# mini_screen.net
KiCad netlist of a schematic drawn in EasyEDA Pro
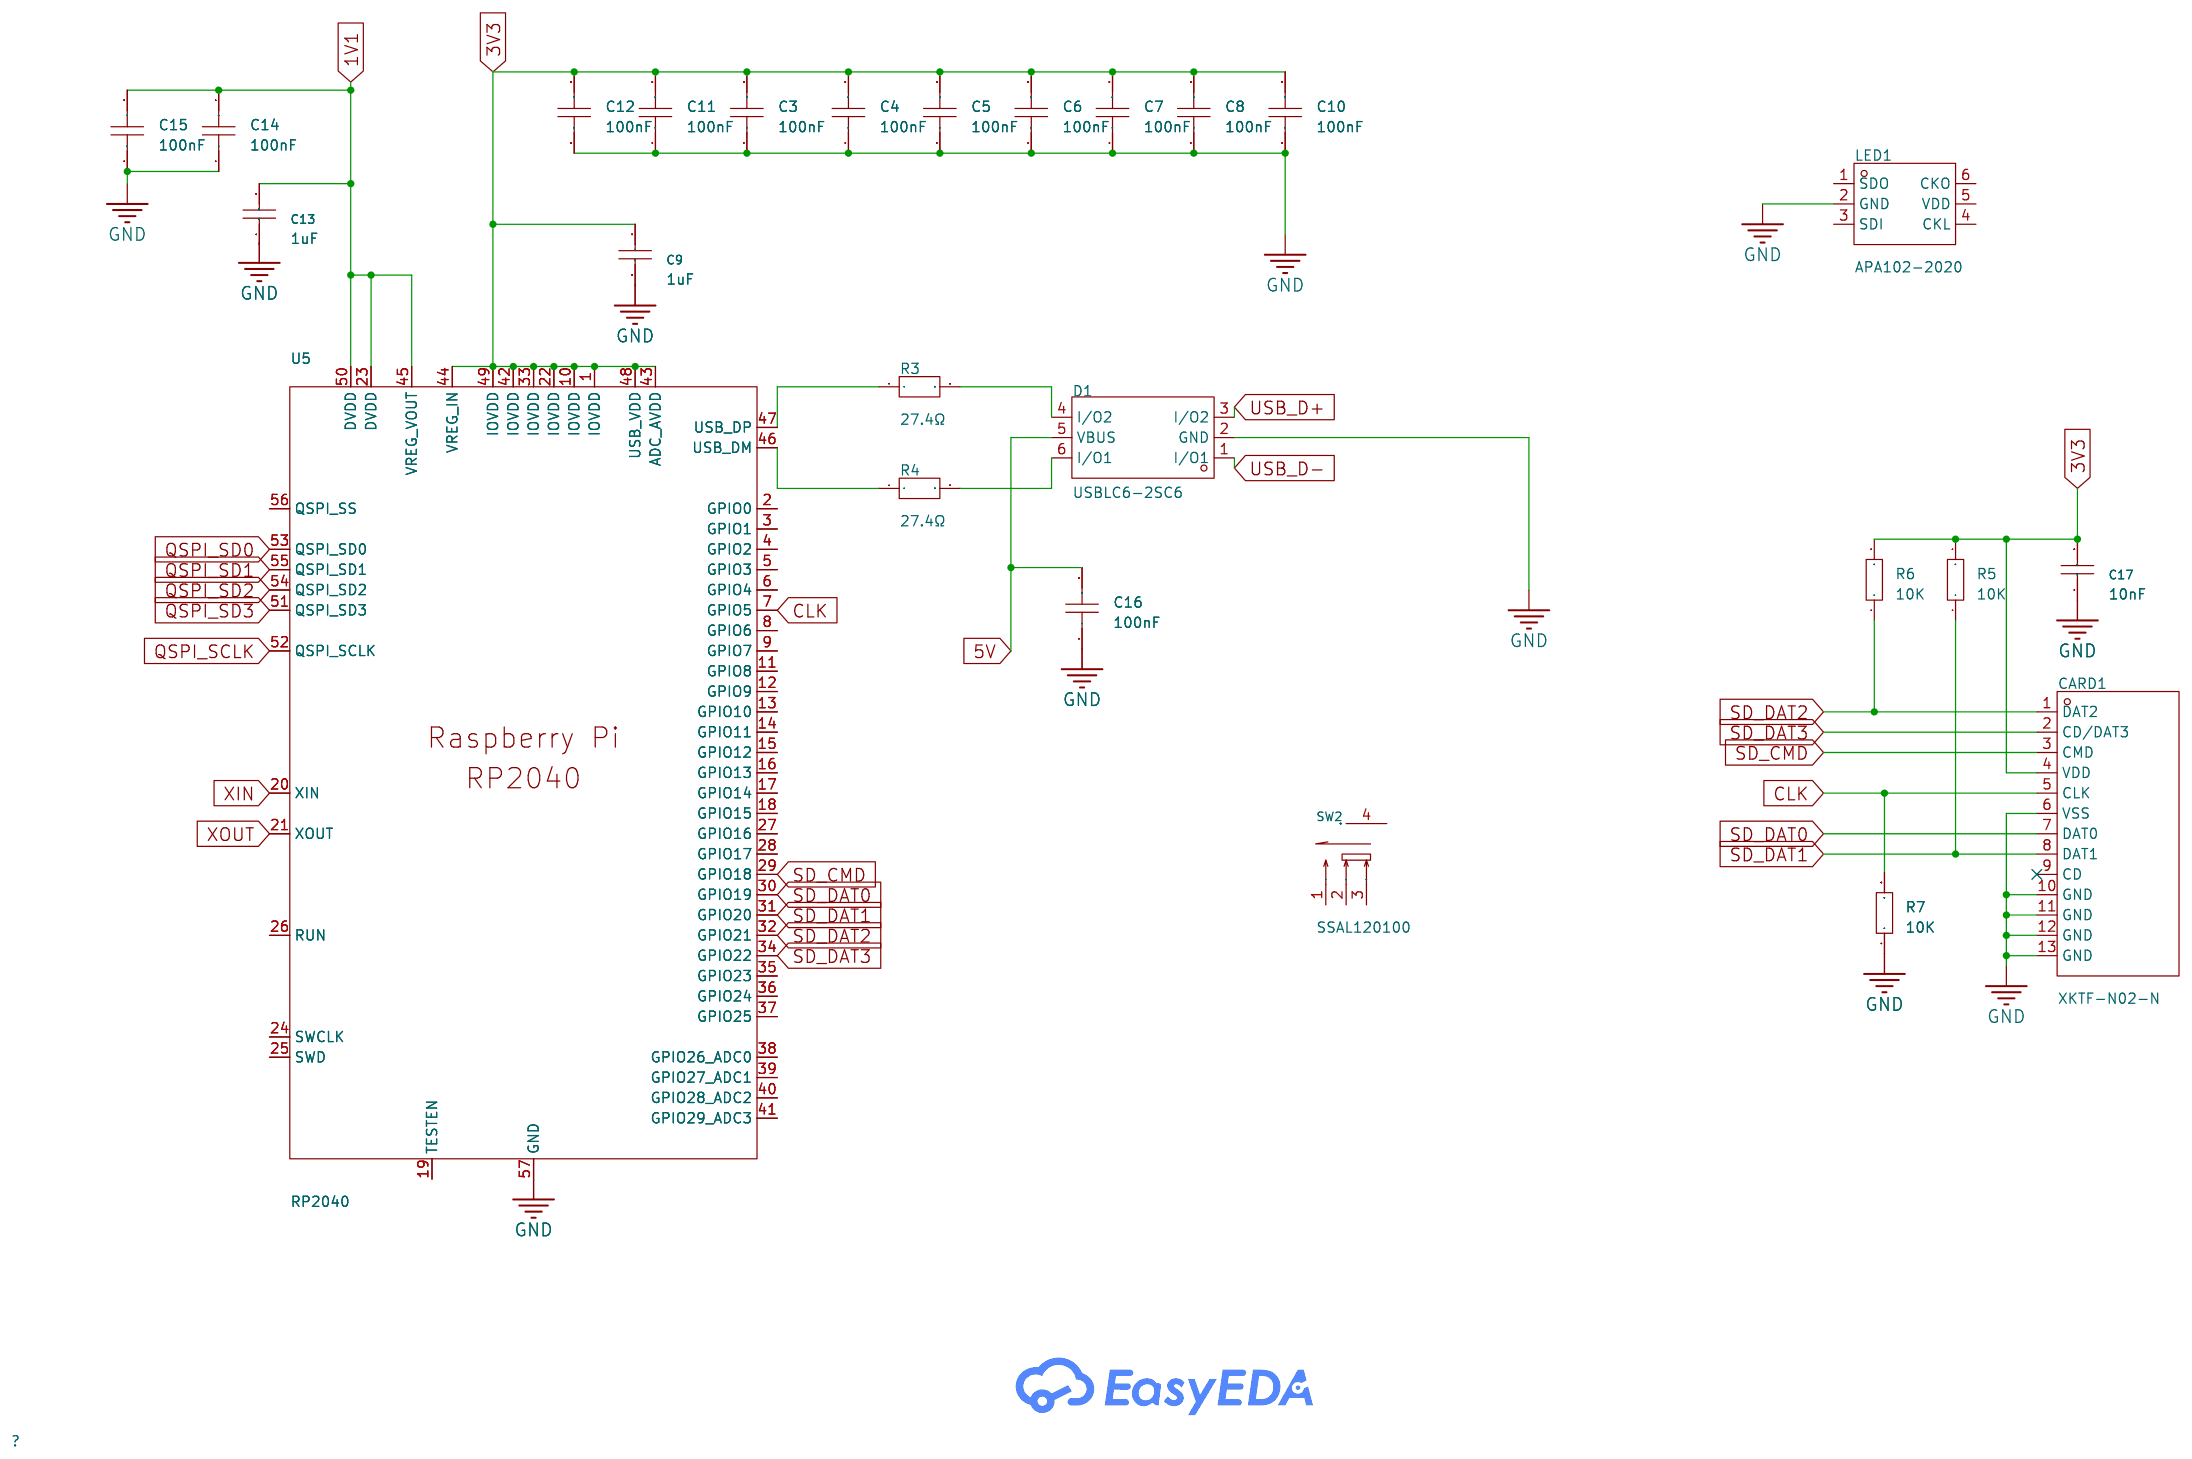
[diagram p0: rp2040]
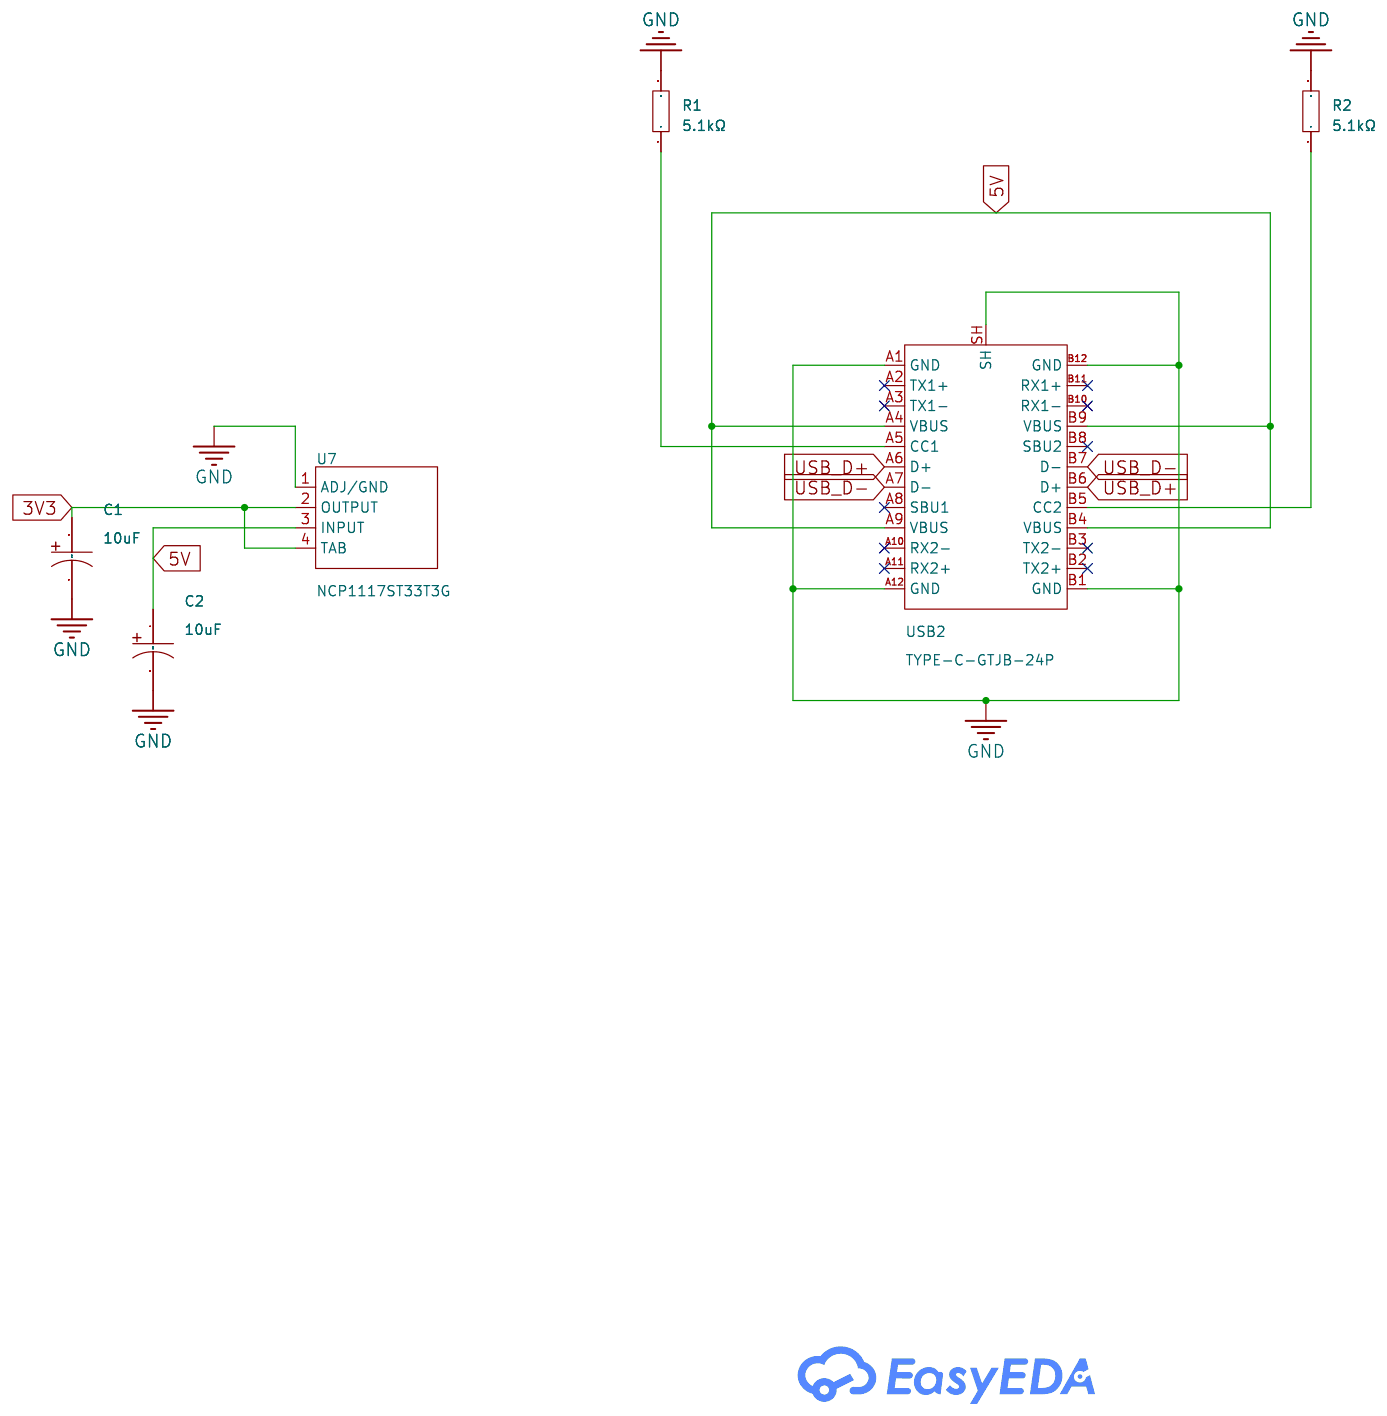
[diagram p1: usbc]
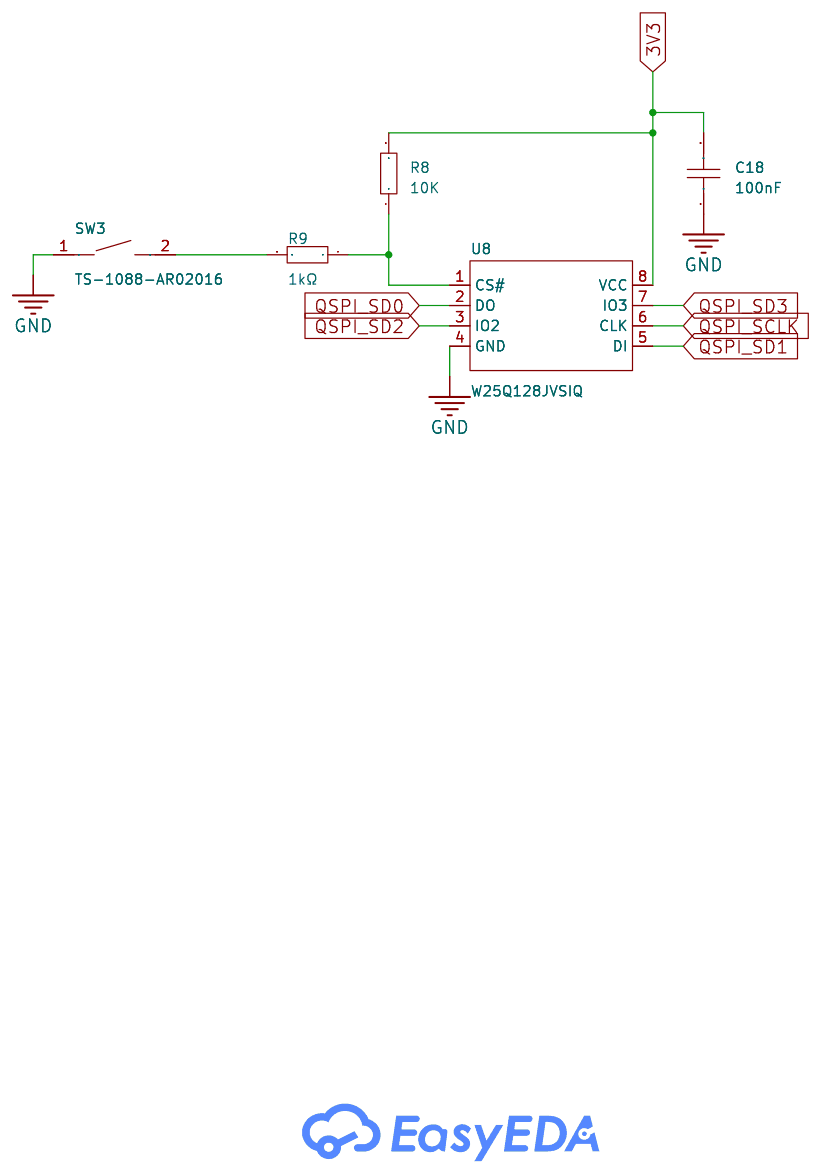
[diagram p2: nand flash]
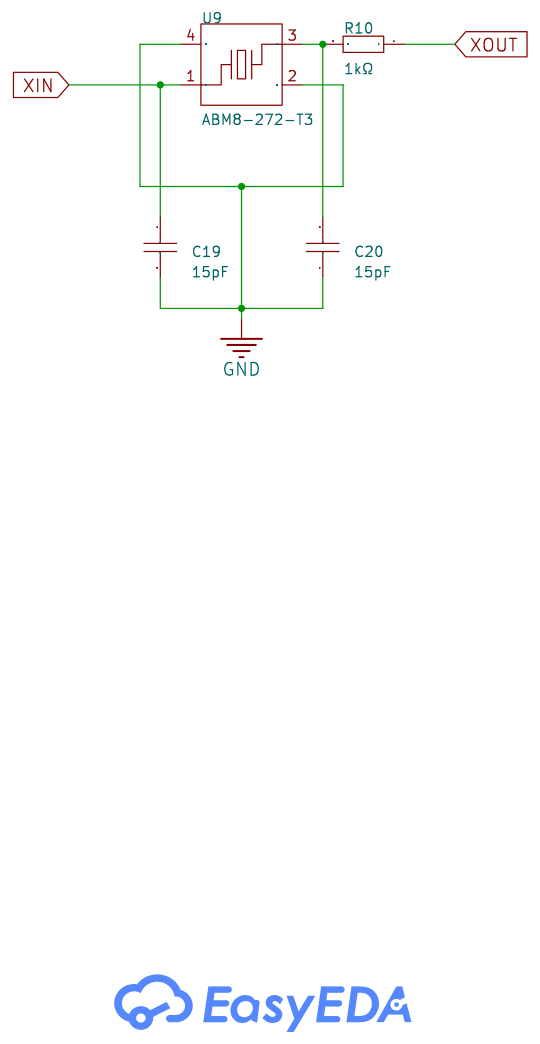
[diagram p3: clock]

(export (version "E")
  (design (tool "Eeschema 10.0.6"))
  (components
    (comp (ref "C3")
      (value "100nF")
      (footprint "easyedapro:C0805")
      (description "Capacitance:100nF Tolerance:±10% Tolerance:±10% Voltage Rating:50V Temperature Coefficient:X7R")
      (fields
        (field (name "Manufacturer Part") "CC0805KRX7R9BB104")
        (field (name "Manufacturer") "YAGEO(国巨)")
      )
      (libsource (lib "easyedapro") (part "CC0805KRX7R9BB104"))
    )
    (comp (ref "C4")
      (value "100nF")
      (footprint "easyedapro:C0805")
      (description "Capacitance:100nF Tolerance:±10% Tolerance:±10% Voltage Rating:50V Temperature Coefficient:X7R")
      (fields
        (field (name "Manufacturer Part") "CC0805KRX7R9BB104")
        (field (name "Manufacturer") "YAGEO(国巨)")
      )
      (libsource (lib "easyedapro") (part "CC0805KRX7R9BB104"))
    )
    (comp (ref "C5")
      (value "100nF")
      (footprint "easyedapro:C0805")
      (description "Capacitance:100nF Tolerance:±10% Tolerance:±10% Voltage Rating:50V Temperature Coefficient:X7R")
      (fields
        (field (name "Manufacturer Part") "CC0805KRX7R9BB104")
        (field (name "Manufacturer") "YAGEO(国巨)")
      )
      (libsource (lib "easyedapro") (part "CC0805KRX7R9BB104"))
    )
    (comp (ref "C6")
      (value "100nF")
      (footprint "easyedapro:C0805")
      (description "Capacitance:100nF Tolerance:±10% Tolerance:±10% Voltage Rating:50V Temperature Coefficient:X7R")
      (fields
        (field (name "Manufacturer Part") "CC0805KRX7R9BB104")
        (field (name "Manufacturer") "YAGEO(国巨)")
      )
      (libsource (lib "easyedapro") (part "CC0805KRX7R9BB104"))
    )
    (comp (ref "C7")
      (value "100nF")
      (footprint "easyedapro:C0805")
      (description "Capacitance:100nF Tolerance:±10% Tolerance:±10% Voltage Rating:50V Temperature Coefficient:X7R")
      (fields
        (field (name "Manufacturer Part") "CC0805KRX7R9BB104")
        (field (name "Manufacturer") "YAGEO(国巨)")
      )
      (libsource (lib "easyedapro") (part "CC0805KRX7R9BB104"))
    )
    (comp (ref "C8")
      (value "100nF")
      (footprint "easyedapro:C0805")
      (description "Capacitance:100nF Tolerance:±10% Tolerance:±10% Voltage Rating:50V Temperature Coefficient:X7R")
      (fields
        (field (name "Manufacturer Part") "CC0805KRX7R9BB104")
        (field (name "Manufacturer") "YAGEO(国巨)")
      )
      (libsource (lib "easyedapro") (part "CC0805KRX7R9BB104"))
    )
    (comp (ref "C9")
      (value "1uF")
      (footprint "easyedapro:C0805")
      (description "Capacitance:1uF Tolerance:±10% Tolerance:±10% Voltage Rating:50V Temperature Coefficient:X7R")
      (fields
        (field (name "Manufacturer Part") "CL21B105KBFNNNE")
        (field (name "Manufacturer") "SAMSUNG(三星)")
      )
      (libsource (lib "easyedapro") (part "CL21B105KBFNNNE"))
    )
    (comp (ref "C10")
      (value "100nF")
      (footprint "easyedapro:C0805")
      (description "Capacitance:100nF Tolerance:±10% Tolerance:±10% Voltage Rating:50V Temperature Coefficient:X7R")
      (fields
        (field (name "Manufacturer Part") "CC0805KRX7R9BB104")
        (field (name "Manufacturer") "YAGEO(国巨)")
      )
      (libsource (lib "easyedapro") (part "CC0805KRX7R9BB104"))
    )
    (comp (ref "C11")
      (value "100nF")
      (footprint "easyedapro:C0805")
      (description "Capacitance:100nF Tolerance:±10% Tolerance:±10% Voltage Rating:50V Temperature Coefficient:X7R")
      (fields
        (field (name "Manufacturer Part") "CC0805KRX7R9BB104")
        (field (name "Manufacturer") "YAGEO(国巨)")
      )
      (libsource (lib "easyedapro") (part "CC0805KRX7R9BB104"))
    )
    (comp (ref "C12")
      (value "100nF")
      (footprint "easyedapro:C0805")
      (description "Capacitance:100nF Tolerance:±10% Tolerance:±10% Voltage Rating:50V Temperature Coefficient:X7R")
      (fields
        (field (name "Manufacturer Part") "CC0805KRX7R9BB104")
        (field (name "Manufacturer") "YAGEO(国巨)")
      )
      (libsource (lib "easyedapro") (part "CC0805KRX7R9BB104"))
    )
    (comp (ref "C13")
      (value "1uF")
      (footprint "easyedapro:C0805")
      (description "Capacitance:1uF Tolerance:±10% Tolerance:±10% Voltage Rating:50V Temperature Coefficient:X7R")
      (fields
        (field (name "Manufacturer Part") "CL21B105KBFNNNE")
        (field (name "Manufacturer") "SAMSUNG(三星)")
      )
      (libsource (lib "easyedapro") (part "CL21B105KBFNNNE"))
    )
    (comp (ref "C14")
      (value "100nF")
      (footprint "easyedapro:C0805")
      (description "Capacitance:100nF Tolerance:±10% Tolerance:±10% Voltage Rating:50V Temperature Coefficient:X7R")
      (fields
        (field (name "Manufacturer Part") "CC0805KRX7R9BB104")
        (field (name "Manufacturer") "YAGEO(国巨)")
      )
      (libsource (lib "easyedapro") (part "CC0805KRX7R9BB104"))
    )
    (comp (ref "C15")
      (value "100nF")
      (footprint "easyedapro:C0805")
      (description "Capacitance:100nF Tolerance:±10% Tolerance:±10% Voltage Rating:50V Temperature Coefficient:X7R")
      (fields
        (field (name "Manufacturer Part") "CC0805KRX7R9BB104")
        (field (name "Manufacturer") "YAGEO(国巨)")
      )
      (libsource (lib "easyedapro") (part "CC0805KRX7R9BB104"))
    )
    (comp (ref "C16")
      (value "100nF")
      (footprint "easyedapro:C0805")
      (description "Capacitance:100nF Tolerance:±10% Tolerance:±10% Voltage Rating:50V Temperature Coefficient:X7R")
      (fields
        (field (name "Manufacturer Part") "CC0805KRX7R9BB104")
        (field (name "Manufacturer") "YAGEO(国巨)")
      )
      (libsource (lib "easyedapro") (part "CC0805KRX7R9BB104"))
    )
    (comp (ref "C17")
      (value "10nF")
      (footprint "easyedapro:C0603")
      (description "Capacitance:10nF Tolerance:±10% Tolerance:±10% Voltage Rating:50V Temperature Coefficient:X7R")
      (fields (field (name "Manufacturer Part") "0603B103K500NT") (field (name "Manufacturer") "FH(风华)"))
      (libsource (lib "easyedapro") (part "0603B103K500NT"))
    )
    (comp (ref "CARD1")
      (value "XKTF-N02-N")
      (footprint "easyedapro:TF-SMD_XKTF-N02-N")
      (fields (field (name "Manufacturer") "XKB Connection(中国星坤)"))
      (libsource (lib "easyedapro") (part "XKTF-N02-N"))
    )
    (comp (ref "D1")
      (value "USBLC6-2SC6")
      (footprint "easyedapro:SOT-23-6_L2.9-W1.6-P0.95-LS2.8-BL")
      (description "Maximum Clamping Voltage:15V Breakdown Voltage:6V Number of Lines:双路 Type:ESD")
      (fields (field (name "Manufacturer") "UMW(友台半导体)"))
      (libsource (lib "easyedapro") (part "USBLC6-2SC6_C2687116"))
    )
    (comp (ref "LED1")
      (value "APA102-2020")
      (footprint "easyedapro:LED-SMD_6P-L2.0-W2.0-P0.80-TL")
      (libsource (lib "easyedapro") (part "APA102-2020"))
    )
    (comp (ref "R3")
      (value "27.4Ω")
      (footprint "easyedapro:R0603")
      (fields (field (name "Manufacturer Part") "FRC0603F27R4TS") (field (name "Manufacturer") "FOJAN(富捷)"))
      (libsource (lib "easyedapro") (part "FRC0603F27R4TS"))
    )
    (comp (ref "R4")
      (value "27.4Ω")
      (footprint "easyedapro:R0603")
      (fields (field (name "Manufacturer Part") "FRC0603F27R4TS") (field (name "Manufacturer") "FOJAN(富捷)"))
      (libsource (lib "easyedapro") (part "FRC0603F27R4TS"))
    )
    (comp (ref "R5") (value "10K") (footprint "easyedapro:R0603") (libsource (lib "easyedapro") (part "Res")))
    (comp (ref "R6") (value "10K") (footprint "easyedapro:R0603") (libsource (lib "easyedapro") (part "Res")))
    (comp (ref "R7") (value "10K") (footprint "easyedapro:R0603") (libsource (lib "easyedapro") (part "Res")))
    (comp (ref "SW2")
      (value "SSAL120100")
      (footprint "easyedapro:SW-SMD_SSAL120100")
      (fields (field (name "Manufacturer") "ALPSALPINE(阿尔卑斯阿尔派)"))
      (libsource (lib "easyedapro") (part "SSAL120100"))
    )
    (comp (ref "U5")
      (value "RP2040")
      (footprint "easyedapro:QFN-56_L7.0-W7.0-P0.40-TL-EP4.0")
      (fields (field (name "Manufacturer") "Raspberry Pi(树莓派)"))
      (libsource (lib "easyedapro") (part "RP2040_C2961140"))
    )
    (comp (ref "C1")
      (value "10uF")
      (footprint "easyedapro:CAP-SMD_BD4.0-L4.3-W4.3-FD")
      (fields (field (name "Manufacturer Part") "EEEHP1A100R") (field (name "Manufacturer") "PANASONIC(松下)"))
      (libsource (lib "easyedapro") (part "EEEHP1A100R"))
    )
    (comp (ref "C2")
      (value "10uF")
      (footprint "easyedapro:CAP-SMD_BD4.0-L4.3-W4.3-FD")
      (fields (field (name "Manufacturer Part") "EEEHP1A100R") (field (name "Manufacturer") "PANASONIC(松下)"))
      (libsource (lib "easyedapro") (part "EEEHP1A100R"))
    )
    (comp (ref "R1")
      (value "5.1kΩ")
      (footprint "easyedapro:R0603")
      (fields
        (field (name "Manufacturer Part") "0603WAF5101T5E")
        (field (name "Manufacturer") "UNI-ROYAL(厚声)")
      )
      (libsource (lib "easyedapro") (part "0603WAF5101T5E"))
    )
    (comp (ref "R2")
      (value "5.1kΩ")
      (footprint "easyedapro:R0603")
      (fields
        (field (name "Manufacturer Part") "0603WAF5101T5E")
        (field (name "Manufacturer") "UNI-ROYAL(厚声)")
      )
      (libsource (lib "easyedapro") (part "0603WAF5101T5E"))
    )
    (comp (ref "U7")
      (value "NCP1117ST33T3G")
      (footprint "easyedapro:SOT-223-3_L6.5-W3.4-P2.30-LS7.0-BR")
      (fields (field (name "Manufacturer") "onsemi(安森美)"))
      (libsource (lib "easyedapro") (part "NCP1117ST33T3G"))
    )
    (comp (ref "USB2")
      (value "TYPE-C-GTJB-24P")
      (footprint "easyedapro:USB-C-SMD_TYPE-C-GTJB-24P")
      (fields (field (name "Manufacturer") "JXTCONN(聚兴泰)"))
      (libsource (lib "easyedapro") (part "TYPE-C-GTJB-24P"))
    )
    (comp (ref "C18")
      (value "100nF")
      (footprint "easyedapro:C0805")
      (description "Capacitance:100nF Tolerance:±10% Tolerance:±10% Voltage Rating:50V Temperature Coefficient:X7R")
      (fields
        (field (name "Manufacturer Part") "CC0805KRX7R9BB104")
        (field (name "Manufacturer") "YAGEO(国巨)")
      )
      (libsource (lib "easyedapro") (part "CC0805KRX7R9BB104"))
    )
    (comp (ref "R8") (value "10K") (footprint "easyedapro:R0603") (libsource (lib "easyedapro") (part "Res")))
    (comp (ref "R9")
      (value "1kΩ")
      (footprint "easyedapro:R0603")
      (fields
        (field (name "Manufacturer Part") "0603WAF1001T5E")
        (field (name "Manufacturer") "UNI-ROYAL(厚声)")
      )
      (libsource (lib "easyedapro") (part "0603WAF1001T5E"))
    )
    (comp (ref "SW3")
      (value "TS-1088-AR02016")
      (footprint "easyedapro:SW-SMD_L3.9-W3.0-P4.45")
      (fields (field (name "Manufacturer") "XUNPU(讯普)"))
      (libsource (lib "easyedapro") (part "TS-1088-AR02016"))
    )
    (comp (ref "U8")
      (value "W25Q128JVSIQ")
      (footprint "easyedapro:SOIC-8_L5.3-W5.3-P1.27-LS8.0-BL")
      (fields (field (name "Manufacturer") "Winbond(华邦)"))
      (libsource (lib "easyedapro") (part "W25Q128JVSIQTR"))
    )
    (comp (ref "C19")
      (value "15pF")
      (footprint "easyedapro:C0603")
      (description "Capacitance:15pF Tolerance:±5% Tolerance:±5% Voltage Rating:50V Temperature Coefficient:C0G")
      (fields
        (field (name "Manufacturer Part") "CL10C150JB8NNNC")
        (field (name "Manufacturer") "SAMSUNG(三星)")
      )
      (libsource (lib "easyedapro") (part "CL10C150JB8NNNC"))
    )
    (comp (ref "C20")
      (value "15pF")
      (footprint "easyedapro:C0603")
      (description "Capacitance:15pF Tolerance:±5% Tolerance:±5% Voltage Rating:50V Temperature Coefficient:C0G")
      (fields
        (field (name "Manufacturer Part") "CL10C150JB8NNNC")
        (field (name "Manufacturer") "SAMSUNG(三星)")
      )
      (libsource (lib "easyedapro") (part "CL10C150JB8NNNC"))
    )
    (comp (ref "R10")
      (value "1kΩ")
      (footprint "easyedapro:R0603")
      (fields
        (field (name "Manufacturer Part") "0603WAF1001T5E")
        (field (name "Manufacturer") "UNI-ROYAL(厚声)")
      )
      (libsource (lib "easyedapro") (part "0603WAF1001T5E"))
    )
    (comp (ref "U9")
      (value "ABM8-272-T3")
      (footprint "easyedapro:CRYSTAL-SMD_4P-L3.2-W2.5-BL")
      (fields (field (name "Manufacturer") "ABRACON"))
      (libsource (lib "easyedapro") (part "ABM8-272-T3_C20625731"))
    )
  )
  (nets
    (net (code "1") (name "1V1") (class "Default")
      (node (ref "C13") (pin "2") (pinfunction "2_2") (pintype "input"))
      (node (ref "C14") (pin "2") (pinfunction "2_2") (pintype "unspecified"))
      (node (ref "C15") (pin "2") (pinfunction "2_2") (pintype "unspecified"))
      (node (ref "U5") (pin "23") (pinfunction "DVDD_23") (pintype "bidirectional"))
      (node (ref "U5") (pin "45") (pinfunction "VREG_VOUT_45") (pintype "bidirectional"))
      (node (ref "U5") (pin "50") (pinfunction "DVDD_50") (pintype "bidirectional"))
    )
    (net (code "2") (name "3V3") (class "Default")
      (node (ref "C1") (pin "1") (pinfunction "1_1") (pintype "unspecified"))
      (node (ref "C10") (pin "2") (pinfunction "2_2") (pintype "unspecified"))
      (node (ref "C11") (pin "2") (pinfunction "2_2") (pintype "unspecified"))
      (node (ref "C12") (pin "2") (pinfunction "2_2") (pintype "unspecified"))
      (node (ref "C17") (pin "2") (pinfunction "2_2") (pintype "input"))
      (node (ref "C18") (pin "2") (pinfunction "2_2") (pintype "unspecified"))
      (node (ref "C3") (pin "2") (pinfunction "2_2") (pintype "unspecified"))
      (node (ref "C4") (pin "2") (pinfunction "2_2") (pintype "unspecified"))
      (node (ref "C5") (pin "2") (pinfunction "2_2") (pintype "unspecified"))
      (node (ref "C6") (pin "2") (pinfunction "2_2") (pintype "unspecified"))
      (node (ref "C7") (pin "2") (pinfunction "2_2") (pintype "unspecified"))
      (node (ref "C8") (pin "2") (pinfunction "2_2") (pintype "unspecified"))
      (node (ref "C9") (pin "2") (pinfunction "2_2") (pintype "input"))
      (node (ref "CARD1") (pin "4") (pinfunction "VDD_4") (pintype "unspecified"))
      (node (ref "R5") (pin "2") (pinfunction "2_2") (pintype "input"))
      (node (ref "R6") (pin "2") (pinfunction "2_2") (pintype "input"))
      (node (ref "R8") (pin "2") (pinfunction "2_2") (pintype "input"))
      (node (ref "U5") (pin "1") (pinfunction "IOVDD_1") (pintype "bidirectional"))
      (node (ref "U5") (pin "10") (pinfunction "IOVDD_10") (pintype "bidirectional"))
      (node (ref "U5") (pin "22") (pinfunction "IOVDD_22") (pintype "bidirectional"))
      (node (ref "U5") (pin "33") (pinfunction "IOVDD_33") (pintype "bidirectional"))
      (node (ref "U5") (pin "42") (pinfunction "IOVDD_42") (pintype "bidirectional"))
      (node (ref "U5") (pin "43") (pinfunction "ADC_AVDD_43") (pintype "bidirectional"))
      (node (ref "U5") (pin "44") (pinfunction "VREG_IN_44") (pintype "bidirectional"))
      (node (ref "U5") (pin "48") (pinfunction "USB_VDD_48") (pintype "bidirectional"))
      (node (ref "U5") (pin "49") (pinfunction "IOVDD_49") (pintype "bidirectional"))
      (node (ref "U7") (pin "2") (pinfunction "OUTPUT_2") (pintype "unspecified"))
      (node (ref "U7") (pin "4") (pinfunction "TAB_4") (pintype "unspecified"))
      (node (ref "U8") (pin "8") (pinfunction "VCC_8") (pintype "unspecified"))
    )
    (net (code "3") (name "5V") (class "Default")
      (node (ref "C16") (pin "2") (pinfunction "2_2") (pintype "unspecified"))
      (node (ref "C2") (pin "1") (pinfunction "1_1") (pintype "unspecified"))
      (node (ref "D1") (pin "5") (pinfunction "VBUS_5") (pintype "unspecified"))
      (node (ref "U7") (pin "3") (pinfunction "INPUT_3") (pintype "unspecified"))
      (node (ref "USB2") (pin "A4") (pinfunction "VBUS_A4") (pintype "unspecified"))
      (node (ref "USB2") (pin "A9") (pinfunction "VBUS_A9") (pintype "unspecified"))
      (node (ref "USB2") (pin "B4") (pinfunction "VBUS_B4") (pintype "unspecified"))
      (node (ref "USB2") (pin "B9") (pinfunction "VBUS_B9") (pintype "unspecified"))
    )
    (net (code "4") (name "CLK") (class "Default")
      (node (ref "CARD1") (pin "5") (pinfunction "CLK_5") (pintype "unspecified"))
      (node (ref "R7") (pin "2") (pinfunction "2_2") (pintype "input"))
      (node (ref "U5") (pin "7") (pinfunction "GPIO5_7") (pintype "bidirectional"))
    )
    (net (code "5") (name "GND") (class "Default")
      (node (ref "C1") (pin "2") (pinfunction "2_2") (pintype "unspecified"))
      (node (ref "C10") (pin "1") (pinfunction "1_1") (pintype "unspecified"))
      (node (ref "C11") (pin "1") (pinfunction "1_1") (pintype "unspecified"))
      (node (ref "C12") (pin "1") (pinfunction "1_1") (pintype "unspecified"))
      (node (ref "C13") (pin "1") (pinfunction "1_1") (pintype "input"))
      (node (ref "C14") (pin "1") (pinfunction "1_1") (pintype "unspecified"))
      (node (ref "C15") (pin "1") (pinfunction "1_1") (pintype "unspecified"))
      (node (ref "C16") (pin "1") (pinfunction "1_1") (pintype "unspecified"))
      (node (ref "C17") (pin "1") (pinfunction "1_1") (pintype "input"))
      (node (ref "C18") (pin "1") (pinfunction "1_1") (pintype "unspecified"))
      (node (ref "C19") (pin "2") (pinfunction "2_2") (pintype "input"))
      (node (ref "C2") (pin "2") (pinfunction "2_2") (pintype "unspecified"))
      (node (ref "C20") (pin "1") (pinfunction "1_1") (pintype "input"))
      (node (ref "C3") (pin "1") (pinfunction "1_1") (pintype "unspecified"))
      (node (ref "C4") (pin "1") (pinfunction "1_1") (pintype "unspecified"))
      (node (ref "C5") (pin "1") (pinfunction "1_1") (pintype "unspecified"))
      (node (ref "C6") (pin "1") (pinfunction "1_1") (pintype "unspecified"))
      (node (ref "C7") (pin "1") (pinfunction "1_1") (pintype "unspecified"))
      (node (ref "C8") (pin "1") (pinfunction "1_1") (pintype "unspecified"))
      (node (ref "C9") (pin "1") (pinfunction "1_1") (pintype "input"))
      (node (ref "CARD1") (pin "10") (pinfunction "GND_10") (pintype "unspecified"))
      (node (ref "CARD1") (pin "11") (pinfunction "GND_11") (pintype "unspecified"))
      (node (ref "CARD1") (pin "12") (pinfunction "GND_12") (pintype "unspecified"))
      (node (ref "CARD1") (pin "13") (pinfunction "GND_13") (pintype "unspecified"))
      (node (ref "CARD1") (pin "6") (pinfunction "VSS_6") (pintype "unspecified"))
      (node (ref "D1") (pin "2") (pinfunction "GND_2") (pintype "unspecified"))
      (node (ref "LED1") (pin "2") (pinfunction "GND_2") (pintype "input"))
      (node (ref "R1") (pin "2") (pinfunction "2_2") (pintype "input"))
      (node (ref "R2") (pin "2") (pinfunction "2_2") (pintype "input"))
      (node (ref "R7") (pin "1") (pinfunction "1_1") (pintype "input"))
      (node (ref "SW3") (pin "1") (pinfunction "1_1") (pintype "unspecified"))
      (node (ref "U5") (pin "57") (pinfunction "GND_57") (pintype "bidirectional"))
      (node (ref "U7") (pin "1") (pinfunction "ADJ/GND_1") (pintype "unspecified"))
      (node (ref "U8") (pin "4") (pinfunction "GND_4") (pintype "unspecified"))
      (node (ref "U9") (pin "2") (pinfunction "GND_2") (pintype "input"))
      (node (ref "U9") (pin "4") (pinfunction "GND_4") (pintype "input"))
      (node (ref "USB2") (pin "A1") (pinfunction "GND_A1") (pintype "unspecified"))
      (node (ref "USB2") (pin "A12") (pinfunction "GND_A12") (pintype "unspecified"))
      (node (ref "USB2") (pin "B1") (pinfunction "GND_B1") (pintype "unspecified"))
      (node (ref "USB2") (pin "B12") (pinfunction "GND_B12") (pintype "unspecified"))
      (node (ref "USB2") (pin "SH") (pinfunction "SH_SH") (pintype "unspecified"))
    )
    (net (code "6") (name "Net-(C20-Pad2)") (class "Default")
      (node (ref "C20") (pin "2") (pinfunction "2_2") (pintype "input"))
      (node (ref "R10") (pin "2") (pinfunction "2_2") (pintype "input"))
      (node (ref "U9") (pin "3") (pinfunction "3_3") (pintype "input"))
    )
    (net (code "7") (name "Net-(D1-I{slash}O1-Pad6)") (class "Default")
      (node (ref "D1") (pin "6") (pinfunction "I/O1_6") (pintype "unspecified"))
      (node (ref "R4") (pin "2") (pinfunction "2_2") (pintype "unspecified"))
    )
    (net (code "8") (name "Net-(D1-I{slash}O2-Pad4)") (class "Default")
      (node (ref "D1") (pin "4") (pinfunction "I/O2_4") (pintype "unspecified"))
      (node (ref "R3") (pin "2") (pinfunction "2_2") (pintype "unspecified"))
    )
    (net (code "9") (name "Net-(R9-Pad2)") (class "Default")
      (node (ref "R9") (pin "2") (pinfunction "2_2") (pintype "input"))
      (node (ref "SW3") (pin "2") (pinfunction "2_2") (pintype "unspecified"))
    )
    (net (code "10") (name "Net-(U5-USB_DM)") (class "Default")
      (node (ref "R4") (pin "1") (pinfunction "1_1") (pintype "unspecified"))
      (node (ref "U5") (pin "46") (pinfunction "USB_DM_46") (pintype "bidirectional"))
    )
    (net (code "11") (name "Net-(U5-USB_DP)") (class "Default")
      (node (ref "R3") (pin "1") (pinfunction "1_1") (pintype "unspecified"))
      (node (ref "U5") (pin "47") (pinfunction "USB_DP_47") (pintype "bidirectional"))
    )
    (net (code "12") (name "Net-(U8-CS#)") (class "Default")
      (node (ref "R8") (pin "1") (pinfunction "1_1") (pintype "input"))
      (node (ref "R9") (pin "1") (pinfunction "1_1") (pintype "input"))
      (node (ref "U8") (pin "1") (pinfunction "CS#_1") (pintype "unspecified"))
    )
    (net (code "13") (name "Net-(USB2-CC1)") (class "Default")
      (node (ref "R1") (pin "1") (pinfunction "1_1") (pintype "input"))
      (node (ref "USB2") (pin "A5") (pinfunction "CC1_A5") (pintype "unspecified"))
    )
    (net (code "14") (name "Net-(USB2-CC2)") (class "Default")
      (node (ref "R2") (pin "1") (pinfunction "1_1") (pintype "input"))
      (node (ref "USB2") (pin "B5") (pinfunction "CC2_B5") (pintype "unspecified"))
    )
    (net (code "15") (name "QSPI_SCLK") (class "Default")
      (node (ref "U5") (pin "52") (pinfunction "QSPI_SCLK_52") (pintype "output"))
      (node (ref "U8") (pin "6") (pinfunction "CLK_6") (pintype "unspecified"))
    )
    (net (code "16") (name "QSPI_SD0") (class "Default")
      (node (ref "U5") (pin "53") (pinfunction "QSPI_SD0_53") (pintype "bidirectional"))
      (node (ref "U8") (pin "2") (pinfunction "DO_2") (pintype "unspecified"))
    )
    (net (code "17") (name "QSPI_SD1") (class "Default")
      (node (ref "U5") (pin "55") (pinfunction "QSPI_SD1_55") (pintype "bidirectional"))
      (node (ref "U8") (pin "5") (pinfunction "DI_5") (pintype "unspecified"))
    )
    (net (code "18") (name "QSPI_SD2") (class "Default")
      (node (ref "U5") (pin "54") (pinfunction "QSPI_SD2_54") (pintype "bidirectional"))
      (node (ref "U8") (pin "3") (pinfunction "IO2_3") (pintype "unspecified"))
    )
    (net (code "19") (name "QSPI_SD3") (class "Default")
      (node (ref "U5") (pin "51") (pinfunction "QSPI_SD3_51") (pintype "bidirectional"))
      (node (ref "U8") (pin "7") (pinfunction "IO3_7") (pintype "unspecified"))
    )
    (net (code "20") (name "SD_CMD") (class "Default")
      (node (ref "CARD1") (pin "3") (pinfunction "CMD_3") (pintype "unspecified"))
      (node (ref "U5") (pin "29") (pinfunction "GPIO18_29") (pintype "bidirectional"))
    )
    (net (code "21") (name "SD_DAT0") (class "Default")
      (node (ref "CARD1") (pin "7") (pinfunction "DAT0_7") (pintype "unspecified"))
      (node (ref "U5") (pin "30") (pinfunction "GPIO19_30") (pintype "bidirectional"))
    )
    (net (code "22") (name "SD_DAT1") (class "Default")
      (node (ref "CARD1") (pin "8") (pinfunction "DAT1_8") (pintype "unspecified"))
      (node (ref "R5") (pin "1") (pinfunction "1_1") (pintype "input"))
      (node (ref "U5") (pin "31") (pinfunction "GPIO20_31") (pintype "bidirectional"))
    )
    (net (code "23") (name "SD_DAT2") (class "Default")
      (node (ref "CARD1") (pin "1") (pinfunction "DAT2_1") (pintype "unspecified"))
      (node (ref "R6") (pin "1") (pinfunction "1_1") (pintype "input"))
      (node (ref "U5") (pin "32") (pinfunction "GPIO21_32") (pintype "bidirectional"))
    )
    (net (code "24") (name "SD_DAT3") (class "Default")
      (node (ref "CARD1") (pin "2") (pinfunction "CD/DAT3_2") (pintype "unspecified"))
      (node (ref "U5") (pin "34") (pinfunction "GPIO22_34") (pintype "bidirectional"))
    )
    (net (code "25") (name "USB_D+") (class "Default")
      (node (ref "D1") (pin "3") (pinfunction "I/O2_3") (pintype "unspecified"))
      (node (ref "USB2") (pin "A6") (pinfunction "D+_A6") (pintype "unspecified"))
      (node (ref "USB2") (pin "B6") (pinfunction "D+_B6") (pintype "unspecified"))
    )
    (net (code "26") (name "USB_D-") (class "Default")
      (node (ref "D1") (pin "1") (pinfunction "I/O1_1") (pintype "unspecified"))
      (node (ref "USB2") (pin "A7") (pinfunction "D-_A7") (pintype "unspecified"))
      (node (ref "USB2") (pin "B7") (pinfunction "D-_B7") (pintype "unspecified"))
    )
    (net (code "27") (name "XIN") (class "Default")
      (node (ref "C19") (pin "1") (pinfunction "1_1") (pintype "input"))
      (node (ref "U5") (pin "20") (pinfunction "XIN_20") (pintype "input"))
      (node (ref "U9") (pin "1") (pinfunction "1_1") (pintype "input"))
    )
    (net (code "28") (name "XOUT") (class "Default")
      (node (ref "R10") (pin "1") (pinfunction "1_1") (pintype "input"))
      (node (ref "U5") (pin "21") (pinfunction "XOUT_21") (pintype "unspecified"))
    )
    (net (code "29") (name "unconnected-(CARD1-CD-Pad9)") (class "Default")
      (node (ref "CARD1") (pin "9") (pinfunction "CD_9") (pintype "unspecified+no_connect"))
    )
    (net (code "30") (name "unconnected-(LED1-CKL-Pad4)") (class "Default")
      (node (ref "LED1") (pin "4") (pinfunction "CKL_4") (pintype "input"))
    )
    (net (code "31") (name "unconnected-(LED1-CKO-Pad6)") (class "Default")
      (node (ref "LED1") (pin "6") (pinfunction "CKO_6") (pintype "input"))
    )
    (net (code "32") (name "unconnected-(LED1-SDI-Pad3)") (class "Default")
      (node (ref "LED1") (pin "3") (pinfunction "SDI_3") (pintype "input"))
    )
    (net (code "33") (name "unconnected-(LED1-SDO-Pad1)") (class "Default")
      (node (ref "LED1") (pin "1") (pinfunction "SDO_1") (pintype "input"))
    )
    (net (code "34") (name "unconnected-(LED1-VDD-Pad5)") (class "Default")
      (node (ref "LED1") (pin "5") (pinfunction "VDD_5") (pintype "input"))
    )
    (net (code "35") (name "unconnected-(SW2-Pad1)") (class "Default")
      (node (ref "SW2") (pin "1") (pinfunction "1_1") (pintype "input"))
    )
    (net (code "36") (name "unconnected-(SW2-Pad2)") (class "Default")
      (node (ref "SW2") (pin "2") (pinfunction "2_2") (pintype "input"))
    )
    (net (code "37") (name "unconnected-(SW2-Pad3)") (class "Default")
      (node (ref "SW2") (pin "3") (pinfunction "3_3") (pintype "input"))
    )
    (net (code "38") (name "unconnected-(SW2-SHELL-Pad4)") (class "Default")
      (node (ref "SW2") (pin "4") (pinfunction "SHELL_4") (pintype "input"))
    )
    (net (code "39") (name "unconnected-(U5-GPIO0-Pad2)") (class "Default")
      (node (ref "U5") (pin "2") (pinfunction "GPIO0_2") (pintype "bidirectional"))
    )
    (net (code "40") (name "unconnected-(U5-GPIO1-Pad3)") (class "Default")
      (node (ref "U5") (pin "3") (pinfunction "GPIO1_3") (pintype "bidirectional"))
    )
    (net (code "41") (name "unconnected-(U5-GPIO2-Pad4)") (class "Default")
      (node (ref "U5") (pin "4") (pinfunction "GPIO2_4") (pintype "bidirectional"))
    )
    (net (code "42") (name "unconnected-(U5-GPIO3-Pad5)") (class "Default")
      (node (ref "U5") (pin "5") (pinfunction "GPIO3_5") (pintype "bidirectional"))
    )
    (net (code "43") (name "unconnected-(U5-GPIO4-Pad6)") (class "Default")
      (node (ref "U5") (pin "6") (pinfunction "GPIO4_6") (pintype "bidirectional"))
    )
    (net (code "44") (name "unconnected-(U5-GPIO6-Pad8)") (class "Default")
      (node (ref "U5") (pin "8") (pinfunction "GPIO6_8") (pintype "bidirectional"))
    )
    (net (code "45") (name "unconnected-(U5-GPIO7-Pad9)") (class "Default")
      (node (ref "U5") (pin "9") (pinfunction "GPIO7_9") (pintype "bidirectional"))
    )
    (net (code "46") (name "unconnected-(U5-GPIO8-Pad11)") (class "Default")
      (node (ref "U5") (pin "11") (pinfunction "GPIO8_11") (pintype "bidirectional"))
    )
    (net (code "47") (name "unconnected-(U5-GPIO9-Pad12)") (class "Default")
      (node (ref "U5") (pin "12") (pinfunction "GPIO9_12") (pintype "bidirectional"))
    )
    (net (code "48") (name "unconnected-(U5-GPIO10-Pad13)") (class "Default")
      (node (ref "U5") (pin "13") (pinfunction "GPIO10_13") (pintype "bidirectional"))
    )
    (net (code "49") (name "unconnected-(U5-GPIO11-Pad14)") (class "Default")
      (node (ref "U5") (pin "14") (pinfunction "GPIO11_14") (pintype "bidirectional"))
    )
    (net (code "50") (name "unconnected-(U5-GPIO12-Pad15)") (class "Default")
      (node (ref "U5") (pin "15") (pinfunction "GPIO12_15") (pintype "bidirectional"))
    )
    (net (code "51") (name "unconnected-(U5-GPIO13-Pad16)") (class "Default")
      (node (ref "U5") (pin "16") (pinfunction "GPIO13_16") (pintype "bidirectional"))
    )
    (net (code "52") (name "unconnected-(U5-GPIO14-Pad17)") (class "Default")
      (node (ref "U5") (pin "17") (pinfunction "GPIO14_17") (pintype "bidirectional"))
    )
    (net (code "53") (name "unconnected-(U5-GPIO15-Pad18)") (class "Default")
      (node (ref "U5") (pin "18") (pinfunction "GPIO15_18") (pintype "bidirectional"))
    )
    (net (code "54") (name "unconnected-(U5-GPIO16-Pad27)") (class "Default")
      (node (ref "U5") (pin "27") (pinfunction "GPIO16_27") (pintype "bidirectional"))
    )
    (net (code "55") (name "unconnected-(U5-GPIO17-Pad28)") (class "Default")
      (node (ref "U5") (pin "28") (pinfunction "GPIO17_28") (pintype "bidirectional"))
    )
    (net (code "56") (name "unconnected-(U5-GPIO23-Pad35)") (class "Default")
      (node (ref "U5") (pin "35") (pinfunction "GPIO23_35") (pintype "bidirectional"))
    )
    (net (code "57") (name "unconnected-(U5-GPIO24-Pad36)") (class "Default")
      (node (ref "U5") (pin "36") (pinfunction "GPIO24_36") (pintype "bidirectional"))
    )
    (net (code "58") (name "unconnected-(U5-GPIO25-Pad37)") (class "Default")
      (node (ref "U5") (pin "37") (pinfunction "GPIO25_37") (pintype "bidirectional"))
    )
    (net (code "59") (name "unconnected-(U5-GPIO26_ADC0-Pad38)") (class "Default")
      (node (ref "U5") (pin "38") (pinfunction "GPIO26_ADC0_38") (pintype "bidirectional"))
    )
    (net (code "60") (name "unconnected-(U5-GPIO27_ADC1-Pad39)") (class "Default")
      (node (ref "U5") (pin "39") (pinfunction "GPIO27_ADC1_39") (pintype "bidirectional"))
    )
    (net (code "61") (name "unconnected-(U5-GPIO28_ADC2-Pad40)") (class "Default")
      (node (ref "U5") (pin "40") (pinfunction "GPIO28_ADC2_40") (pintype "bidirectional"))
    )
    (net (code "62") (name "unconnected-(U5-GPIO29_ADC3-Pad41)") (class "Default")
      (node (ref "U5") (pin "41") (pinfunction "GPIO29_ADC3_41") (pintype "bidirectional"))
    )
    (net (code "63") (name "unconnected-(U5-QSPI_SS-Pad56)") (class "Default")
      (node (ref "U5") (pin "56") (pinfunction "QSPI_SS_56") (pintype "bidirectional"))
    )
    (net (code "64") (name "unconnected-(U5-RUN-Pad26)") (class "Default")
      (node (ref "U5") (pin "26") (pinfunction "RUN_26") (pintype "input"))
    )
    (net (code "65") (name "unconnected-(U5-SWCLK-Pad24)") (class "Default")
      (node (ref "U5") (pin "24") (pinfunction "SWCLK_24") (pintype "output"))
    )
    (net (code "66") (name "unconnected-(U5-SWD-Pad25)") (class "Default")
      (node (ref "U5") (pin "25") (pinfunction "SWD_25") (pintype "bidirectional"))
    )
    (net (code "67") (name "unconnected-(U5-TESTEN-Pad19)") (class "Default")
      (node (ref "U5") (pin "19") (pinfunction "TESTEN_19") (pintype "unspecified"))
    )
    (net (code "68") (name "unconnected-(USB2-RX1+-PadB11)") (class "Default")
      (node (ref "USB2") (pin "B11") (pinfunction "RX1+_B11") (pintype "unspecified+no_connect"))
    )
    (net (code "69") (name "unconnected-(USB2-RX1--PadB10)") (class "Default")
      (node (ref "USB2") (pin "B10") (pinfunction "RX1-_B10") (pintype "unspecified+no_connect"))
    )
    (net (code "70") (name "unconnected-(USB2-RX2+-PadA11)") (class "Default")
      (node (ref "USB2") (pin "A11") (pinfunction "RX2+_A11") (pintype "unspecified+no_connect"))
    )
    (net (code "71") (name "unconnected-(USB2-RX2--PadA10)") (class "Default")
      (node (ref "USB2") (pin "A10") (pinfunction "RX2-_A10") (pintype "unspecified+no_connect"))
    )
    (net (code "72") (name "unconnected-(USB2-SBU1-PadA8)") (class "Default")
      (node (ref "USB2") (pin "A8") (pinfunction "SBU1_A8") (pintype "unspecified+no_connect"))
    )
    (net (code "73") (name "unconnected-(USB2-SBU2-PadB8)") (class "Default")
      (node (ref "USB2") (pin "B8") (pinfunction "SBU2_B8") (pintype "unspecified+no_connect"))
    )
    (net (code "74") (name "unconnected-(USB2-TX1+-PadA2)") (class "Default")
      (node (ref "USB2") (pin "A2") (pinfunction "TX1+_A2") (pintype "unspecified+no_connect"))
    )
    (net (code "75") (name "unconnected-(USB2-TX1--PadA3)") (class "Default")
      (node (ref "USB2") (pin "A3") (pinfunction "TX1-_A3") (pintype "unspecified+no_connect"))
    )
    (net (code "76") (name "unconnected-(USB2-TX2+-PadB2)") (class "Default")
      (node (ref "USB2") (pin "B2") (pinfunction "TX2+_B2") (pintype "unspecified+no_connect"))
    )
    (net (code "77") (name "unconnected-(USB2-TX2--PadB3)") (class "Default")
      (node (ref "USB2") (pin "B3") (pinfunction "TX2-_B3") (pintype "unspecified+no_connect"))
    )
  )
)
